# psoc1_20246_B.net
KiCad netlist of a schematic drawn in EAGLE
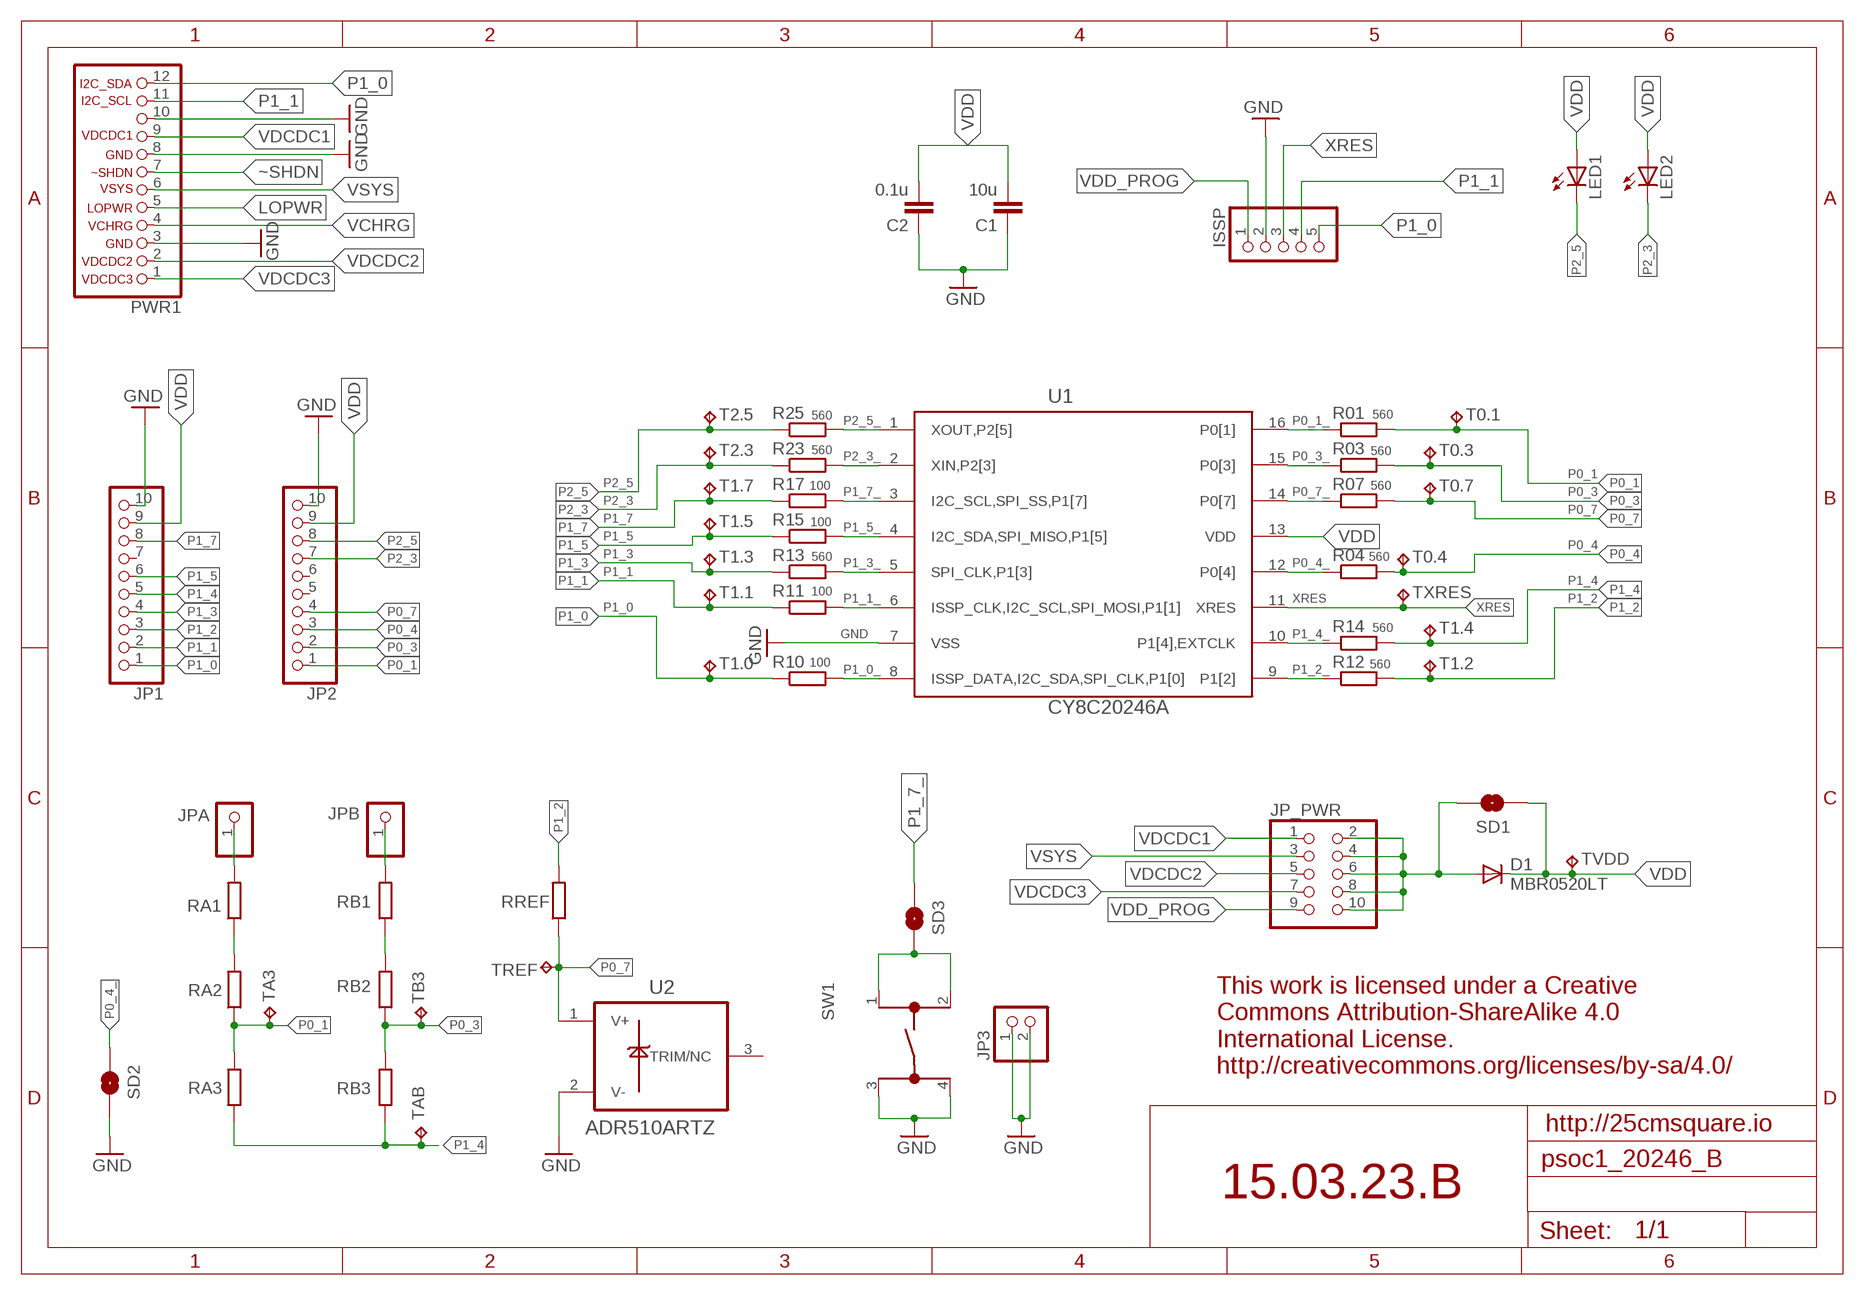
[diagram p0: schematic, sheet 1]

(export (version "E")
  (design (tool "Eeschema 10.0.6"))
  (components
    (comp (ref "C1")
      (value "10u")
      (footprint "eagle-import:C1206")
      (libsource (lib "eagle-import") (part "C-EUC1206"))
    )
    (comp (ref "C2")
      (value "0.1u")
      (footprint "eagle-import:C0603")
      (libsource (lib "eagle-import") (part "resistor_C-EUC0603"))
    )
    (comp (ref "D1")
      (value "MBR0520LT")
      (footprint "eagle-import:SOD123")
      (libsource (lib "eagle-import") (part "MBR0520LT"))
    )
    (comp (ref "ISSP")
      (value "PINHD-1X5/90")
      (footprint "eagle-import:1X05_90")
      (libsource (lib "eagle-import") (part "PINHD-1X5/90"))
    )
    (comp (ref "JP1")
      (value "PINHD-1X10")
      (footprint "eagle-import:1X10")
      (libsource (lib "eagle-import") (part "PINHD-1X10"))
    )
    (comp (ref "JP2")
      (value "PINHD-1X10")
      (footprint "eagle-import:1X10")
      (libsource (lib "eagle-import") (part "PINHD-1X10"))
    )
    (comp (ref "JP3")
      (value "PINHD-1X2")
      (footprint "eagle-import:1X02")
      (libsource (lib "eagle-import") (part "PINHD-1X2"))
    )
    (comp (ref "JPA")
      (value "PINHD-1X1")
      (footprint "eagle-import:1X01")
      (libsource (lib "eagle-import") (part "PINHD-1X1"))
    )
    (comp (ref "JPB")
      (value "PINHD-1X1")
      (footprint "eagle-import:1X01")
      (libsource (lib "eagle-import") (part "PINHD-1X1"))
    )
    (comp (ref "JP_PWR")
      (value "PINHD-2X5")
      (footprint "eagle-import:2X05")
      (libsource (lib "eagle-import") (part "PINHD-2X5"))
    )
    (comp (ref "LED1")
      (value "LEDSML0603")
      (footprint "eagle-import:SML0603")
      (libsource (lib "eagle-import") (part "LEDSML0603"))
    )
    (comp (ref "LED2")
      (value "LEDSML0603")
      (footprint "eagle-import:SML0603")
      (libsource (lib "eagle-import") (part "LEDSML0603"))
    )
    (comp (ref "PWR1")
      (value "LIWE_12_PIN_PWR")
      (footprint "eagle-import:LIWE_12_PIN")
      (libsource (lib "eagle-import") (part "LIWE_12_PIN_PWR"))
    )
    (comp (ref "R01")
      (value "560")
      (footprint "eagle-import:R0603")
      (libsource (lib "eagle-import") (part "R-EU_R0603"))
    )
    (comp (ref "R03")
      (value "560")
      (footprint "eagle-import:R0603")
      (libsource (lib "eagle-import") (part "R-EU_R0603"))
    )
    (comp (ref "R04")
      (value "560")
      (footprint "eagle-import:R0603")
      (libsource (lib "eagle-import") (part "R-EU_R0603"))
    )
    (comp (ref "R07")
      (value "560")
      (footprint "eagle-import:R0603")
      (libsource (lib "eagle-import") (part "R-EU_R0603"))
    )
    (comp (ref "R10")
      (value "100")
      (footprint "eagle-import:R0603")
      (libsource (lib "eagle-import") (part "R-EU_R0603"))
    )
    (comp (ref "R11")
      (value "100")
      (footprint "eagle-import:R0603")
      (libsource (lib "eagle-import") (part "R-EU_R0603"))
    )
    (comp (ref "R12")
      (value "560")
      (footprint "eagle-import:R0603")
      (libsource (lib "eagle-import") (part "R-EU_R0603"))
    )
    (comp (ref "R13")
      (value "560")
      (footprint "eagle-import:R0603")
      (libsource (lib "eagle-import") (part "R-EU_R0603"))
    )
    (comp (ref "R14")
      (value "560")
      (footprint "eagle-import:R0603")
      (libsource (lib "eagle-import") (part "R-EU_R0603"))
    )
    (comp (ref "R15")
      (value "100")
      (footprint "eagle-import:R0603")
      (libsource (lib "eagle-import") (part "R-EU_R0603"))
    )
    (comp (ref "R17")
      (value "100")
      (footprint "eagle-import:R0603")
      (libsource (lib "eagle-import") (part "R-EU_R0603"))
    )
    (comp (ref "R23")
      (value "560")
      (footprint "eagle-import:R0603")
      (libsource (lib "eagle-import") (part "R-EU_R0603"))
    )
    (comp (ref "R25")
      (value "560")
      (footprint "eagle-import:R0603")
      (libsource (lib "eagle-import") (part "R-EU_R0603"))
    )
    (comp (ref "RA1")
      (value "R-EU_R0603")
      (footprint "eagle-import:R0603")
      (libsource (lib "eagle-import") (part "R-EU_R0603"))
    )
    (comp (ref "RA2")
      (value "R-EU_R0603")
      (footprint "eagle-import:R0603")
      (libsource (lib "eagle-import") (part "R-EU_R0603"))
    )
    (comp (ref "RA3")
      (value "R-EU_R0603")
      (footprint "eagle-import:R0603")
      (libsource (lib "eagle-import") (part "R-EU_R0603"))
    )
    (comp (ref "RB1")
      (value "R-EU_R0603")
      (footprint "eagle-import:R0603")
      (libsource (lib "eagle-import") (part "R-EU_R0603"))
    )
    (comp (ref "RB2")
      (value "R-EU_R0603")
      (footprint "eagle-import:R0603")
      (libsource (lib "eagle-import") (part "R-EU_R0603"))
    )
    (comp (ref "RB3")
      (value "R-EU_R0603")
      (footprint "eagle-import:R0603")
      (libsource (lib "eagle-import") (part "R-EU_R0603"))
    )
    (comp (ref "RREF")
      (value "R-EU_R0603")
      (footprint "eagle-import:R0603")
      (libsource (lib "eagle-import") (part "R-EU_R0603"))
    )
    (comp (ref "SD1")
      (value "SOLDERJUMPERNO")
      (footprint "eagle-import:SJ_2S-NO")
      (libsource (lib "eagle-import") (part "SOLDERJUMPERNO"))
    )
    (comp (ref "SD2")
      (value "SOLDERJUMPERNO")
      (footprint "eagle-import:SJ_2S-NO")
      (libsource (lib "eagle-import") (part "SOLDERJUMPERNO"))
    )
    (comp (ref "SD3")
      (value "SOLDERJUMPERNO")
      (footprint "eagle-import:SJ_2S-NO")
      (libsource (lib "eagle-import") (part "SOLDERJUMPERNO"))
    )
    (comp (ref "SW1")
      (value "FSM4JH")
      (footprint "eagle-import:FSM4JH")
      (libsource (lib "eagle-import") (part "FSM4JH"))
    )
    (comp (ref "T0.1")
      (value "TPTP14R")
      (footprint "eagle-import:TP14R")
      (libsource (lib "eagle-import") (part "TPTP14R"))
    )
    (comp (ref "T0.3")
      (value "TPTP14R")
      (footprint "eagle-import:TP14R")
      (libsource (lib "eagle-import") (part "TPTP14R"))
    )
    (comp (ref "T0.4")
      (value "TPTP14R")
      (footprint "eagle-import:TP14R")
      (libsource (lib "eagle-import") (part "TPTP14R"))
    )
    (comp (ref "T0.7")
      (value "TPTP14R")
      (footprint "eagle-import:TP14R")
      (libsource (lib "eagle-import") (part "TPTP14R"))
    )
    (comp (ref "T1.0")
      (value "TPTP14R")
      (footprint "eagle-import:TP14R")
      (libsource (lib "eagle-import") (part "TPTP14R"))
    )
    (comp (ref "T1.1")
      (value "TPTP14R")
      (footprint "eagle-import:TP14R")
      (libsource (lib "eagle-import") (part "TPTP14R"))
    )
    (comp (ref "T1.2")
      (value "TPTP14R")
      (footprint "eagle-import:TP14R")
      (libsource (lib "eagle-import") (part "TPTP14R"))
    )
    (comp (ref "T1.3")
      (value "TPTP14R")
      (footprint "eagle-import:TP14R")
      (libsource (lib "eagle-import") (part "TPTP14R"))
    )
    (comp (ref "T1.4")
      (value "TPTP14R")
      (footprint "eagle-import:TP14R")
      (libsource (lib "eagle-import") (part "TPTP14R"))
    )
    (comp (ref "T1.5")
      (value "TPTP14R")
      (footprint "eagle-import:TP14R")
      (libsource (lib "eagle-import") (part "TPTP14R"))
    )
    (comp (ref "T1.7")
      (value "TPTP14R")
      (footprint "eagle-import:TP14R")
      (libsource (lib "eagle-import") (part "TPTP14R"))
    )
    (comp (ref "T2.3")
      (value "TPTP14R")
      (footprint "eagle-import:TP14R")
      (libsource (lib "eagle-import") (part "TPTP14R"))
    )
    (comp (ref "T2.5")
      (value "TPTP14R")
      (footprint "eagle-import:TP14R")
      (libsource (lib "eagle-import") (part "TPTP14R"))
    )
    (comp (ref "TA3")
      (value "TPTP14R")
      (footprint "eagle-import:TP14R")
      (libsource (lib "eagle-import") (part "TPTP14R"))
    )
    (comp (ref "TAB")
      (value "TPTP14R")
      (footprint "eagle-import:TP14R")
      (libsource (lib "eagle-import") (part "TPTP14R"))
    )
    (comp (ref "TB3")
      (value "TPTP14R")
      (footprint "eagle-import:TP14R")
      (libsource (lib "eagle-import") (part "TPTP14R"))
    )
    (comp (ref "TREF")
      (value "TPTP14R")
      (footprint "eagle-import:TP14R")
      (libsource (lib "eagle-import") (part "TPTP14R"))
    )
    (comp (ref "TVDD")
      (value "TPTP14R")
      (footprint "eagle-import:TP14R")
      (libsource (lib "eagle-import") (part "TPTP14R"))
    )
    (comp (ref "TXRES")
      (value "TPTP14R")
      (footprint "eagle-import:TP14R")
      (libsource (lib "eagle-import") (part "TPTP14R"))
    )
    (comp (ref "U1")
      (value "CY8C20246A")
      (footprint "eagle-import:QFN16_3X3_NOEPAD")
      (libsource (lib "eagle-import") (part "CY8C20246A"))
    )
    (comp (ref "U2")
      (value "ADR510ARTZ")
      (footprint "eagle-import:SOT95P237X112-3N")
      (fields (field (name "MPN") "ADR510ARTZ-REEL7"))
      (libsource (lib "eagle-import") (part "ADR510ARTZ-REEL7"))
    )
  )
  (nets
    (net (code "1") (name "/P0_1_") (class "Default")
      (node (ref "R01") (pin "1") (pinfunction "1_1") (pintype "passive"))
      (node (ref "U1") (pin "16") (pinfunction "P0[1]_16") (pintype "bidirectional"))
    )
    (net (code "2") (name "/P0_3_") (class "Default")
      (node (ref "R03") (pin "1") (pinfunction "1_1") (pintype "passive"))
      (node (ref "U1") (pin "15") (pinfunction "P0[3]_15") (pintype "bidirectional"))
    )
    (net (code "3") (name "/P0_7_") (class "Default")
      (node (ref "R07") (pin "1") (pinfunction "1_1") (pintype "passive"))
      (node (ref "U1") (pin "14") (pinfunction "P0[7]_14") (pintype "bidirectional"))
    )
    (net (code "4") (name "/P1_0_") (class "Default")
      (node (ref "R10") (pin "2") (pinfunction "2_2") (pintype "passive"))
      (node (ref "U1") (pin "8") (pinfunction "ISSP_DATA,I2C_SDA,SPI_CLK,P1[0]_8") (pintype "bidirectional"))
    )
    (net (code "5") (name "/P1_1_") (class "Default")
      (node (ref "R11") (pin "2") (pinfunction "2_2") (pintype "passive"))
      (node (ref "U1") (pin "6") (pinfunction "ISSP_CLK,I2C_SCL,SPI_MOSI,P1[1]_6") (pintype "bidirectional"))
    )
    (net (code "6") (name "/P1_2_") (class "Default")
      (node (ref "R12") (pin "1") (pinfunction "1_1") (pintype "passive"))
      (node (ref "U1") (pin "9") (pinfunction "P1[2]_9") (pintype "bidirectional"))
    )
    (net (code "7") (name "/P1_3_") (class "Default")
      (node (ref "R13") (pin "2") (pinfunction "2_2") (pintype "passive"))
      (node (ref "U1") (pin "5") (pinfunction "SPI_CLK,P1[3]_5") (pintype "bidirectional"))
    )
    (net (code "8") (name "/P1_4_") (class "Default")
      (node (ref "R14") (pin "1") (pinfunction "1_1") (pintype "passive"))
      (node (ref "U1") (pin "10") (pinfunction "P1[4],EXTCLK_10") (pintype "bidirectional"))
    )
    (net (code "9") (name "/P1_5_") (class "Default")
      (node (ref "R15") (pin "2") (pinfunction "2_2") (pintype "passive"))
      (node (ref "U1") (pin "4") (pinfunction "I2C_SDA,SPI_MISO,P1[5]_4") (pintype "bidirectional"))
    )
    (net (code "10") (name "/P2_3_") (class "Default")
      (node (ref "R23") (pin "2") (pinfunction "2_2") (pintype "passive"))
      (node (ref "U1") (pin "2") (pinfunction "XIN,P2[3]_2") (pintype "bidirectional"))
    )
    (net (code "11") (name "/P2_5_") (class "Default")
      (node (ref "R25") (pin "2") (pinfunction "2_2") (pintype "passive"))
      (node (ref "U1") (pin "1") (pinfunction "XOUT,P2[5]_1") (pintype "bidirectional"))
    )
    (net (code "12") (name "/~{SHDN}") (class "Default")
      (node (ref "PWR1") (pin "7") (pinfunction "7_7") (pintype "passive"))
    )
    (net (code "13") (name "GND") (class "Default")
      (node (ref "C1") (pin "1") (pinfunction "1_1") (pintype "passive"))
      (node (ref "C2") (pin "1") (pinfunction "1_1") (pintype "passive"))
      (node (ref "ISSP") (pin "2") (pinfunction "2_2") (pintype "passive"))
      (node (ref "JP1") (pin "10") (pinfunction "10_10") (pintype "passive"))
      (node (ref "JP2") (pin "10") (pinfunction "10_10") (pintype "passive"))
      (node (ref "JP3") (pin "1") (pinfunction "1_1") (pintype "passive"))
      (node (ref "JP3") (pin "2") (pinfunction "2_2") (pintype "passive"))
      (node (ref "PWR1") (pin "10") (pinfunction "10_10") (pintype "passive"))
      (node (ref "PWR1") (pin "3") (pinfunction "3_3") (pintype "passive"))
      (node (ref "PWR1") (pin "8") (pinfunction "8_8") (pintype "passive"))
      (node (ref "SD2") (pin "2") (pinfunction "2_2") (pintype "passive"))
      (node (ref "SW1") (pin "3") (pinfunction "3_3") (pintype "passive"))
      (node (ref "SW1") (pin "4") (pinfunction "4_4") (pintype "passive"))
      (node (ref "U1") (pin "7") (pinfunction "VSS_7") (pintype "power_in"))
      (node (ref "U2") (pin "2") (pinfunction "V-_2") (pintype "power_in"))
    )
    (net (code "14") (name "LOPWR") (class "Default")
      (node (ref "PWR1") (pin "5") (pinfunction "5_5") (pintype "passive"))
    )
    (net (code "15") (name "Net-(D1-PadA)") (class "Default")
      (node (ref "D1") (pin "A") (pinfunction "A_A") (pintype "passive"))
      (node (ref "JP_PWR") (pin "10") (pinfunction "10_10") (pintype "passive"))
      (node (ref "JP_PWR") (pin "2") (pinfunction "2_2") (pintype "passive"))
      (node (ref "JP_PWR") (pin "4") (pinfunction "4_4") (pintype "passive"))
      (node (ref "JP_PWR") (pin "6") (pinfunction "6_6") (pintype "passive"))
      (node (ref "JP_PWR") (pin "8") (pinfunction "8_8") (pintype "passive"))
      (node (ref "SD1") (pin "2") (pinfunction "2_2") (pintype "passive"))
    )
    (net (code "16") (name "Net-(JPA-Pad1)") (class "Default")
      (node (ref "JPA") (pin "1") (pinfunction "1_1") (pintype "passive"))
      (node (ref "RA1") (pin "2") (pinfunction "2_2") (pintype "passive"))
    )
    (net (code "17") (name "Net-(JPB-Pad1)") (class "Default")
      (node (ref "JPB") (pin "1") (pinfunction "1_1") (pintype "passive"))
      (node (ref "RB1") (pin "2") (pinfunction "2_2") (pintype "passive"))
    )
    (net (code "18") (name "Net-(RA1-Pad1)") (class "Default")
      (node (ref "RA1") (pin "1") (pinfunction "1_1") (pintype "passive"))
      (node (ref "RA2") (pin "2") (pinfunction "2_2") (pintype "passive"))
    )
    (net (code "19") (name "Net-(RB1-Pad1)") (class "Default")
      (node (ref "RB1") (pin "1") (pinfunction "1_1") (pintype "passive"))
      (node (ref "RB2") (pin "2") (pinfunction "2_2") (pintype "passive"))
    )
    (net (code "20") (name "Net-(SD3-Pad2)") (class "Default")
      (node (ref "SD3") (pin "2") (pinfunction "2_2") (pintype "passive"))
      (node (ref "SW1") (pin "1") (pinfunction "1_1") (pintype "passive"))
      (node (ref "SW1") (pin "2") (pinfunction "2_2") (pintype "passive"))
    )
    (net (code "21") (name "P0_1") (class "Default")
      (node (ref "JP2") (pin "1") (pinfunction "1_1") (pintype "passive"))
      (node (ref "R01") (pin "2") (pinfunction "2_2") (pintype "passive"))
      (node (ref "RA2") (pin "1") (pinfunction "1_1") (pintype "passive"))
      (node (ref "RA3") (pin "2") (pinfunction "2_2") (pintype "passive"))
      (node (ref "T0.1") (pin "TP") (pinfunction "TP_TP") (pintype "input"))
      (node (ref "TA3") (pin "TP") (pinfunction "TP_TP") (pintype "input"))
    )
    (net (code "22") (name "P0_3") (class "Default")
      (node (ref "JP2") (pin "2") (pinfunction "2_2") (pintype "passive"))
      (node (ref "R03") (pin "2") (pinfunction "2_2") (pintype "passive"))
      (node (ref "RB2") (pin "1") (pinfunction "1_1") (pintype "passive"))
      (node (ref "RB3") (pin "2") (pinfunction "2_2") (pintype "passive"))
      (node (ref "T0.3") (pin "TP") (pinfunction "TP_TP") (pintype "input"))
      (node (ref "TB3") (pin "TP") (pinfunction "TP_TP") (pintype "input"))
    )
    (net (code "23") (name "P0_4") (class "Default")
      (node (ref "JP2") (pin "3") (pinfunction "3_3") (pintype "passive"))
      (node (ref "R04") (pin "2") (pinfunction "2_2") (pintype "passive"))
      (node (ref "T0.4") (pin "TP") (pinfunction "TP_TP") (pintype "input"))
    )
    (net (code "24") (name "P0_4_") (class "Default")
      (node (ref "R04") (pin "1") (pinfunction "1_1") (pintype "passive"))
      (node (ref "SD2") (pin "1") (pinfunction "1_1") (pintype "passive"))
      (node (ref "U1") (pin "12") (pinfunction "P0[4]_12") (pintype "bidirectional"))
    )
    (net (code "25") (name "P0_7") (class "Default")
      (node (ref "JP2") (pin "4") (pinfunction "4_4") (pintype "passive"))
      (node (ref "R07") (pin "2") (pinfunction "2_2") (pintype "passive"))
      (node (ref "RREF") (pin "1") (pinfunction "1_1") (pintype "passive"))
      (node (ref "T0.7") (pin "TP") (pinfunction "TP_TP") (pintype "input"))
      (node (ref "TREF") (pin "TP") (pinfunction "TP_TP") (pintype "input"))
      (node (ref "U2") (pin "1") (pinfunction "V+_1") (pintype "power_in"))
    )
    (net (code "26") (name "P1_0") (class "Default")
      (node (ref "ISSP") (pin "5") (pinfunction "5_5") (pintype "passive"))
      (node (ref "JP1") (pin "1") (pinfunction "1_1") (pintype "passive"))
      (node (ref "PWR1") (pin "12") (pinfunction "12_12") (pintype "passive"))
      (node (ref "R10") (pin "1") (pinfunction "1_1") (pintype "passive"))
      (node (ref "T1.0") (pin "TP") (pinfunction "TP_TP") (pintype "input"))
    )
    (net (code "27") (name "P1_1") (class "Default")
      (node (ref "ISSP") (pin "4") (pinfunction "4_4") (pintype "passive"))
      (node (ref "JP1") (pin "2") (pinfunction "2_2") (pintype "passive"))
      (node (ref "PWR1") (pin "11") (pinfunction "11_11") (pintype "passive"))
      (node (ref "R11") (pin "1") (pinfunction "1_1") (pintype "passive"))
      (node (ref "T1.1") (pin "TP") (pinfunction "TP_TP") (pintype "input"))
    )
    (net (code "28") (name "P1_2") (class "Default")
      (node (ref "JP1") (pin "3") (pinfunction "3_3") (pintype "passive"))
      (node (ref "R12") (pin "2") (pinfunction "2_2") (pintype "passive"))
      (node (ref "RREF") (pin "2") (pinfunction "2_2") (pintype "passive"))
      (node (ref "T1.2") (pin "TP") (pinfunction "TP_TP") (pintype "input"))
    )
    (net (code "29") (name "P1_3") (class "Default")
      (node (ref "JP1") (pin "4") (pinfunction "4_4") (pintype "passive"))
      (node (ref "R13") (pin "1") (pinfunction "1_1") (pintype "passive"))
      (node (ref "T1.3") (pin "TP") (pinfunction "TP_TP") (pintype "input"))
    )
    (net (code "30") (name "P1_4") (class "Default")
      (node (ref "JP1") (pin "5") (pinfunction "5_5") (pintype "passive"))
      (node (ref "R14") (pin "2") (pinfunction "2_2") (pintype "passive"))
      (node (ref "RA3") (pin "1") (pinfunction "1_1") (pintype "passive"))
      (node (ref "RB3") (pin "1") (pinfunction "1_1") (pintype "passive"))
      (node (ref "T1.4") (pin "TP") (pinfunction "TP_TP") (pintype "input"))
      (node (ref "TAB") (pin "TP") (pinfunction "TP_TP") (pintype "input"))
    )
    (net (code "31") (name "P1_5") (class "Default")
      (node (ref "JP1") (pin "6") (pinfunction "6_6") (pintype "passive"))
      (node (ref "R15") (pin "1") (pinfunction "1_1") (pintype "passive"))
      (node (ref "T1.5") (pin "TP") (pinfunction "TP_TP") (pintype "input"))
    )
    (net (code "32") (name "P1_7") (class "Default")
      (node (ref "JP1") (pin "8") (pinfunction "8_8") (pintype "passive"))
      (node (ref "R17") (pin "1") (pinfunction "1_1") (pintype "passive"))
      (node (ref "T1.7") (pin "TP") (pinfunction "TP_TP") (pintype "input"))
    )
    (net (code "33") (name "P1_7_") (class "Default")
      (node (ref "R17") (pin "2") (pinfunction "2_2") (pintype "passive"))
      (node (ref "SD3") (pin "1") (pinfunction "1_1") (pintype "passive"))
      (node (ref "U1") (pin "3") (pinfunction "I2C_SCL,SPI_SS,P1[7]_3") (pintype "bidirectional"))
    )
    (net (code "34") (name "P2_3") (class "Default")
      (node (ref "JP2") (pin "7") (pinfunction "7_7") (pintype "passive"))
      (node (ref "LED2") (pin "C") (pinfunction "C_C") (pintype "passive"))
      (node (ref "R23") (pin "1") (pinfunction "1_1") (pintype "passive"))
      (node (ref "T2.3") (pin "TP") (pinfunction "TP_TP") (pintype "input"))
    )
    (net (code "35") (name "P2_5") (class "Default")
      (node (ref "JP2") (pin "8") (pinfunction "8_8") (pintype "passive"))
      (node (ref "LED1") (pin "C") (pinfunction "C_C") (pintype "passive"))
      (node (ref "R25") (pin "1") (pinfunction "1_1") (pintype "passive"))
      (node (ref "T2.5") (pin "TP") (pinfunction "TP_TP") (pintype "input"))
    )
    (net (code "36") (name "VCHRG") (class "Default")
      (node (ref "PWR1") (pin "4") (pinfunction "4_4") (pintype "passive"))
    )
    (net (code "37") (name "VDCDC1") (class "Default")
      (node (ref "JP_PWR") (pin "1") (pinfunction "1_1") (pintype "passive"))
      (node (ref "PWR1") (pin "9") (pinfunction "9_9") (pintype "passive"))
    )
    (net (code "38") (name "VDCDC2") (class "Default")
      (node (ref "JP_PWR") (pin "5") (pinfunction "5_5") (pintype "passive"))
      (node (ref "PWR1") (pin "2") (pinfunction "2_2") (pintype "passive"))
    )
    (net (code "39") (name "VDCDC3") (class "Default")
      (node (ref "JP_PWR") (pin "7") (pinfunction "7_7") (pintype "passive"))
      (node (ref "PWR1") (pin "1") (pinfunction "1_1") (pintype "passive"))
    )
    (net (code "40") (name "VDD") (class "Default")
      (node (ref "C1") (pin "2") (pinfunction "2_2") (pintype "passive"))
      (node (ref "C2") (pin "2") (pinfunction "2_2") (pintype "passive"))
      (node (ref "D1") (pin "C") (pinfunction "C_C") (pintype "passive"))
      (node (ref "JP1") (pin "9") (pinfunction "9_9") (pintype "passive"))
      (node (ref "JP2") (pin "9") (pinfunction "9_9") (pintype "passive"))
      (node (ref "LED1") (pin "A") (pinfunction "A_A") (pintype "passive"))
      (node (ref "LED2") (pin "A") (pinfunction "A_A") (pintype "passive"))
      (node (ref "SD1") (pin "1") (pinfunction "1_1") (pintype "passive"))
      (node (ref "TVDD") (pin "TP") (pinfunction "TP_TP") (pintype "input"))
      (node (ref "U1") (pin "13") (pinfunction "VDD_13") (pintype "power_in"))
    )
    (net (code "41") (name "VDD_PROG") (class "Default")
      (node (ref "ISSP") (pin "1") (pinfunction "1_1") (pintype "passive"))
      (node (ref "JP_PWR") (pin "9") (pinfunction "9_9") (pintype "passive"))
    )
    (net (code "42") (name "VSYS") (class "Default")
      (node (ref "JP_PWR") (pin "3") (pinfunction "3_3") (pintype "passive"))
      (node (ref "PWR1") (pin "6") (pinfunction "6_6") (pintype "passive"))
    )
    (net (code "43") (name "XRES") (class "Default")
      (node (ref "ISSP") (pin "3") (pinfunction "3_3") (pintype "passive"))
      (node (ref "TXRES") (pin "TP") (pinfunction "TP_TP") (pintype "input"))
      (node (ref "U1") (pin "11") (pinfunction "XRES_11") (pintype "bidirectional"))
    )
    (net (code "44") (name "unconnected-(JP1-Pad7)") (class "Default")
      (node (ref "JP1") (pin "7") (pinfunction "7_7") (pintype "passive"))
    )
    (net (code "45") (name "unconnected-(JP2-Pad5)") (class "Default")
      (node (ref "JP2") (pin "5") (pinfunction "5_5") (pintype "passive"))
    )
    (net (code "46") (name "unconnected-(JP2-Pad6)") (class "Default")
      (node (ref "JP2") (pin "6") (pinfunction "6_6") (pintype "passive"))
    )
    (net (code "47") (name "unconnected-(U2-TRIM{slash}NC-Pad3)") (class "Default")
      (node (ref "U2") (pin "3") (pinfunction "TRIM/NC_3") (pintype "passive"))
    )
  )
)
